# Main_MCU_ATSAME54.net
KiCad netlist of a schematic drawn in Altium Designer
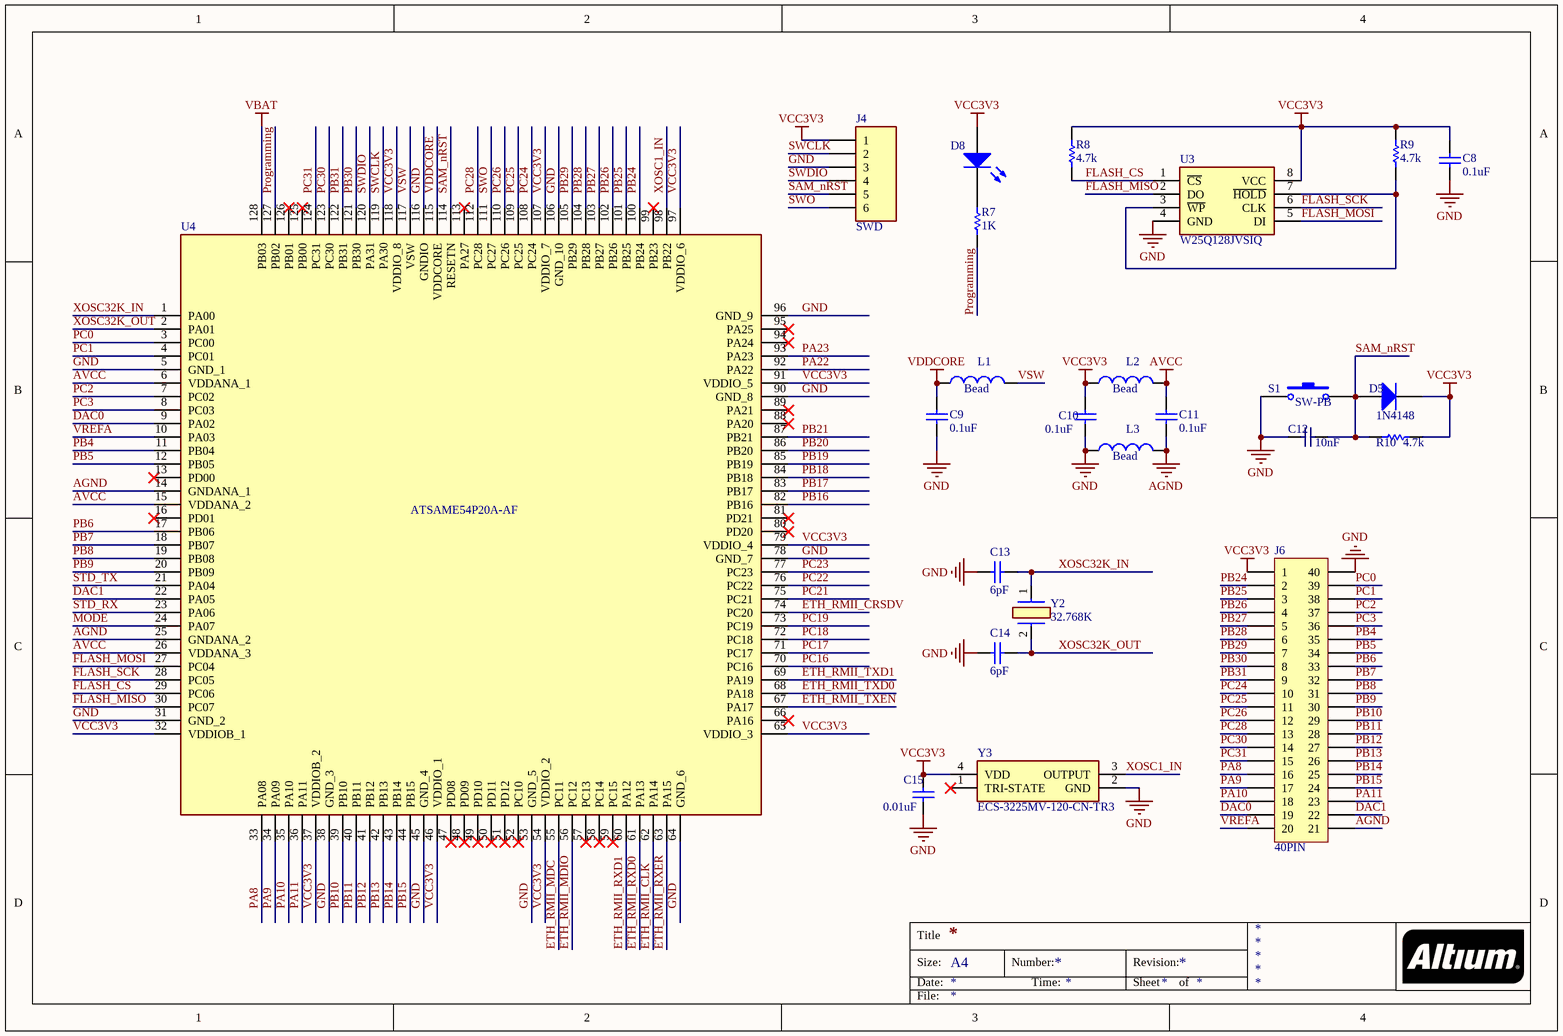
[diagram p0: Main_MCU_ATSAME54.SchDoc]

(export (version "E")
  (design (tool "Eeschema 10.0.6"))
  (components
    (comp (ref "C8")
      (value "0.1uF")
      (footprint "SMD0603")
      (description "Capacitor (Semiconductor SIM Model)")
      (fields (field (name "PUBLISHER") "Altium Limited"))
      (libsource (lib "Miscellaneous Devices") (part "Cap Semi"))
    )
    (comp (ref "C9")
      (value "0.1uF")
      (footprint "SMD0603")
      (description "Capacitor (Semiconductor SIM Model)")
      (fields (field (name "PUBLISHER") "Altium Limited"))
      (libsource (lib "Miscellaneous Devices") (part "Cap Semi"))
    )
    (comp (ref "C10")
      (value "0.1uF")
      (footprint "SMD0603")
      (description "Capacitor (Semiconductor SIM Model)")
      (fields (field (name "PUBLISHER") "Altium Limited"))
      (libsource (lib "Miscellaneous Devices") (part "Cap Semi"))
    )
    (comp (ref "C11")
      (value "0.1uF")
      (footprint "SMD0603")
      (description "Capacitor (Semiconductor SIM Model)")
      (fields (field (name "PUBLISHER") "Altium Limited"))
      (libsource (lib "Miscellaneous Devices") (part "Cap Semi"))
    )
    (comp (ref "C12")
      (value "10nF")
      (footprint "SMD0603")
      (description "Capacitor (Semiconductor SIM Model)")
      (libsource (lib "SRV8") (part "Cap"))
    )
    (comp (ref "C13")
      (value "6pF")
      (footprint "SMD0603")
      (description "Capacitor (Semiconductor SIM Model)")
      (fields (field (name "PUBLISHER") "Altium Limited"))
      (libsource (lib "Miscellaneous Devices") (part "Cap Semi"))
    )
    (comp (ref "C14")
      (value "6pF")
      (footprint "SMD0603")
      (description "Capacitor (Semiconductor SIM Model)")
      (fields (field (name "PUBLISHER") "Altium Limited"))
      (libsource (lib "Miscellaneous Devices") (part "Cap Semi"))
    )
    (comp (ref "C15")
      (value "0.01uF")
      (footprint "SMD0603")
      (description "Capacitor (Semiconductor SIM Model)")
      (fields (field (name "PUBLISHER") "Altium Limited"))
      (libsource (lib "Miscellaneous Devices") (part "Cap Semi"))
    )
    (comp (ref "D5")
      (value "1N4148")
      (footprint "1N4148")
      (description "Diode")
      (fields (field (name "PUBLISHER") "Altium Limited"))
      (libsource (lib "SRV8") (part "Diode 1N4148"))
    )
    (comp (ref "D8")
      (value "LED0")
      (footprint "SMD0603_LED")
      (description "Typical INFRARED GaAs LED")
      (fields (field (name "PUBLISHER") "Altium Limited"))
      (libsource (lib "Miscellaneous Devices") (part "LED0"))
    )
    (comp (ref "J4") (value "SWD") (footprint "ISP") (libsource (lib "ATSAME54p20a_Ethernet") (part "SWD")))
    (comp (ref "J6")
      (value "40PIN")
      (footprint "40PIN")
      (libsource (lib "ATSAME54p20a_Ethernet") (part "2x20_header"))
    )
    (comp (ref "L1")
      (value "Bead")
      (footprint "SMD0603")
      (description "Inductor")
      (fields (field (name "PUBLISHER") "Altium Limited"))
      (libsource (lib "Miscellaneous Devices") (part "Inductor"))
    )
    (comp (ref "L2")
      (value "Bead")
      (footprint "SMD0603")
      (description "Inductor")
      (fields (field (name "PUBLISHER") "Altium Limited"))
      (libsource (lib "Miscellaneous Devices") (part "Inductor"))
    )
    (comp (ref "L3")
      (value "Bead")
      (footprint "SMD0603")
      (description "Inductor")
      (fields (field (name "PUBLISHER") "Altium Limited"))
      (libsource (lib "Miscellaneous Devices") (part "Inductor"))
    )
    (comp (ref "R7")
      (value "1K")
      (footprint "SMD0603")
      (description "Semiconductor Resistor")
      (fields (field (name "PUBLISHER") "Altium Limited"))
      (libsource (lib "Miscellaneous Devices") (part "Res Semi"))
    )
    (comp (ref "R8")
      (value "4.7k")
      (footprint "SMD0603")
      (description "Semiconductor Resistor")
      (libsource (lib "*") (part "Res"))
    )
    (comp (ref "R9")
      (value "4.7k")
      (footprint "SMD0603")
      (description "Semiconductor Resistor")
      (libsource (lib "*") (part "Res"))
    )
    (comp (ref "R10")
      (value "4.7k")
      (footprint "SMD0603")
      (description "Semiconductor Resistor")
      (fields (field (name "Comment") "4.7K"))
      (libsource (lib "*") (part "Res"))
    )
    (comp (ref "S1")
      (value "SW-PB")
      (footprint "Button")
      (description "Switch")
      (fields (field (name "PUBLISHER") "Altium Limited"))
      (libsource (lib "Miscellaneous Devices") (part "SW-PB"))
    )
    (comp (ref "U3")
      (value "W25Q128JVSIQ")
      (footprint "ATSAME54p20a_Ethernet:SOIC127P790X216-8N")
      (description "Integrated Circuit")
      (fields (field (name "MOUSER2 PART NUMBER") "454-W25Q128JVSIQ"))
      (libsource (lib "ATSAME54p20a_Ethernet") (part "W25Q128JVSIQ"))
    )
    (comp (ref "U4")
      (value "ATSAME54P20A-AF")
      (footprint "QFP40P1600X1600X120-128N")
      (description "Integrated Circuit")
      (fields (field (name "MOUSER2 PART NUMBER") "556-ATSAME54P20A-AF"))
      (libsource (lib "ATSAME54p20a_Ethernet") (part "ATSAME54P20A-AF"))
    )
    (comp (ref "Y2")
      (value "32.768K")
      (footprint "ATSAME54p20a_Ethernet:ECS327634RTR")
      (description "Crystal or Oscillator")
      (fields (field (name "MANUFACTURER_PART_NUMBER") "ECS-.327-6-34R-TR"))
      (libsource (lib "ATSAME54_DEVB") (part "ECS-.327-6-34R-TR"))
    )
    (comp (ref "Y3")
      (value "ECS-3225MV-120-CN-TR3")
      (footprint "OSC3225")
      (description "Crystal or Oscillator")
      (libsource (lib "ATSAME54p20a_Ethernet") (part "ECS-3225MV-120-CN-TR3"))
    )
  )
  (nets
    (net (code "1") (name "/DAC0") (class "Default")
      (node (ref "J6") (pin "19") (pinfunction "19_19") (pintype "passive"))
      (node (ref "U4") (pin "9") (pinfunction "PA02_9") (pintype "passive"))
    )
    (net (code "2") (name "/DAC1") (class "Default")
      (node (ref "J6") (pin "22") (pinfunction "22_22") (pintype "passive"))
      (node (ref "U4") (pin "22") (pinfunction "PA05_22") (pintype "passive"))
    )
    (net (code "3") (name "/ETH_RMII_CLK") (class "Default")
      (node (ref "U4") (pin "62") (pinfunction "PA14_62") (pintype "passive"))
    )
    (net (code "4") (name "/ETH_RMII_CRSDV") (class "Default")
      (node (ref "U4") (pin "74") (pinfunction "PC20_74") (pintype "passive"))
    )
    (net (code "5") (name "/ETH_RMII_MDC") (class "Default")
      (node (ref "U4") (pin "55") (pinfunction "PC11_55") (pintype "passive"))
    )
    (net (code "6") (name "/ETH_RMII_MDIO") (class "Default")
      (node (ref "U4") (pin "56") (pinfunction "PC12_56") (pintype "passive"))
    )
    (net (code "7") (name "/ETH_RMII_RXD0") (class "Default")
      (node (ref "U4") (pin "61") (pinfunction "PA13_61") (pintype "passive"))
    )
    (net (code "8") (name "/ETH_RMII_RXD1") (class "Default")
      (node (ref "U4") (pin "60") (pinfunction "PA12_60") (pintype "passive"))
    )
    (net (code "9") (name "/ETH_RMII_RXER") (class "Default")
      (node (ref "U4") (pin "63") (pinfunction "PA15_63") (pintype "passive"))
    )
    (net (code "10") (name "/ETH_RMII_TXD0") (class "Default")
      (node (ref "U4") (pin "68") (pinfunction "PA18_68") (pintype "passive"))
    )
    (net (code "11") (name "/ETH_RMII_TXD1") (class "Default")
      (node (ref "U4") (pin "69") (pinfunction "PA19_69") (pintype "passive"))
    )
    (net (code "12") (name "/ETH_RMII_TXEN") (class "Default")
      (node (ref "U4") (pin "67") (pinfunction "PA17_67") (pintype "passive"))
    )
    (net (code "13") (name "/FLASH_CS") (class "Default")
      (node (ref "R8") (pin "1") (pinfunction "1_1") (pintype "passive"))
      (node (ref "U3") (pin "1") (pinfunction "~{CS}_1") (pintype "passive"))
      (node (ref "U4") (pin "29") (pinfunction "PC06_29") (pintype "passive"))
    )
    (net (code "14") (name "/FLASH_MISO") (class "Default")
      (node (ref "U3") (pin "2") (pinfunction "DO_2") (pintype "passive"))
      (node (ref "U4") (pin "30") (pinfunction "PC07_30") (pintype "passive"))
    )
    (net (code "15") (name "/FLASH_MOSI") (class "Default")
      (node (ref "U3") (pin "5") (pinfunction "DI_5") (pintype "passive"))
      (node (ref "U4") (pin "27") (pinfunction "PC04_27") (pintype "passive"))
    )
    (net (code "16") (name "/FLASH_SCK") (class "Default")
      (node (ref "U3") (pin "6") (pinfunction "CLK_6") (pintype "passive"))
      (node (ref "U4") (pin "28") (pinfunction "PC05_28") (pintype "passive"))
    )
    (net (code "17") (name "/MODE") (class "Default")
      (node (ref "U4") (pin "24") (pinfunction "PA07_24") (pintype "passive"))
    )
    (net (code "18") (name "/PA8") (class "Default")
      (node (ref "J6") (pin "16") (pinfunction "16_16") (pintype "passive"))
      (node (ref "U4") (pin "33") (pinfunction "PA08_33") (pintype "passive"))
    )
    (net (code "19") (name "/PA9") (class "Default")
      (node (ref "J6") (pin "17") (pinfunction "17_17") (pintype "passive"))
      (node (ref "U4") (pin "34") (pinfunction "PA09_34") (pintype "passive"))
    )
    (net (code "20") (name "/PA10") (class "Default")
      (node (ref "J6") (pin "18") (pinfunction "18_18") (pintype "passive"))
      (node (ref "U4") (pin "35") (pinfunction "PA10_35") (pintype "passive"))
    )
    (net (code "21") (name "/PA11") (class "Default")
      (node (ref "J6") (pin "23") (pinfunction "23_23") (pintype "passive"))
      (node (ref "U4") (pin "36") (pinfunction "PA11_36") (pintype "passive"))
    )
    (net (code "22") (name "/PA22") (class "Default")
      (node (ref "U4") (pin "92") (pinfunction "PA22_92") (pintype "passive"))
    )
    (net (code "23") (name "/PA23") (class "Default")
      (node (ref "U4") (pin "93") (pinfunction "PA23_93") (pintype "passive"))
    )
    (net (code "24") (name "/PB4") (class "Default")
      (node (ref "J6") (pin "35") (pinfunction "35_35") (pintype "passive"))
      (node (ref "U4") (pin "11") (pinfunction "PB04_11") (pintype "passive"))
    )
    (net (code "25") (name "/PB5") (class "Default")
      (node (ref "J6") (pin "34") (pinfunction "34_34") (pintype "passive"))
      (node (ref "U4") (pin "12") (pinfunction "PB05_12") (pintype "passive"))
    )
    (net (code "26") (name "/PB6") (class "Default")
      (node (ref "J6") (pin "33") (pinfunction "33_33") (pintype "passive"))
      (node (ref "U4") (pin "17") (pinfunction "PB06_17") (pintype "passive"))
    )
    (net (code "27") (name "/PB7") (class "Default")
      (node (ref "J6") (pin "32") (pinfunction "32_32") (pintype "passive"))
      (node (ref "U4") (pin "18") (pinfunction "PB07_18") (pintype "passive"))
    )
    (net (code "28") (name "/PB8") (class "Default")
      (node (ref "J6") (pin "31") (pinfunction "31_31") (pintype "passive"))
      (node (ref "U4") (pin "19") (pinfunction "PB08_19") (pintype "passive"))
    )
    (net (code "29") (name "/PB9") (class "Default")
      (node (ref "J6") (pin "30") (pinfunction "30_30") (pintype "passive"))
      (node (ref "U4") (pin "20") (pinfunction "PB09_20") (pintype "passive"))
    )
    (net (code "30") (name "/PB10") (class "Default")
      (node (ref "J6") (pin "29") (pinfunction "29_29") (pintype "passive"))
      (node (ref "U4") (pin "39") (pinfunction "PB10_39") (pintype "passive"))
    )
    (net (code "31") (name "/PB11") (class "Default")
      (node (ref "J6") (pin "28") (pinfunction "28_28") (pintype "passive"))
      (node (ref "U4") (pin "40") (pinfunction "PB11_40") (pintype "passive"))
    )
    (net (code "32") (name "/PB12") (class "Default")
      (node (ref "J6") (pin "27") (pinfunction "27_27") (pintype "passive"))
      (node (ref "U4") (pin "41") (pinfunction "PB12_41") (pintype "passive"))
    )
    (net (code "33") (name "/PB13") (class "Default")
      (node (ref "J6") (pin "26") (pinfunction "26_26") (pintype "passive"))
      (node (ref "U4") (pin "42") (pinfunction "PB13_42") (pintype "passive"))
    )
    (net (code "34") (name "/PB14") (class "Default")
      (node (ref "J6") (pin "25") (pinfunction "25_25") (pintype "passive"))
      (node (ref "U4") (pin "43") (pinfunction "PB14_43") (pintype "passive"))
    )
    (net (code "35") (name "/PB15") (class "Default")
      (node (ref "J6") (pin "24") (pinfunction "24_24") (pintype "passive"))
      (node (ref "U4") (pin "44") (pinfunction "PB15_44") (pintype "passive"))
    )
    (net (code "36") (name "/PB16") (class "Default")
      (node (ref "U4") (pin "82") (pinfunction "PB16_82") (pintype "passive"))
    )
    (net (code "37") (name "/PB17") (class "Default")
      (node (ref "U4") (pin "83") (pinfunction "PB17_83") (pintype "passive"))
    )
    (net (code "38") (name "/PB18") (class "Default")
      (node (ref "U4") (pin "84") (pinfunction "PB18_84") (pintype "passive"))
    )
    (net (code "39") (name "/PB19") (class "Default")
      (node (ref "U4") (pin "85") (pinfunction "PB19_85") (pintype "passive"))
    )
    (net (code "40") (name "/PB20") (class "Default")
      (node (ref "U4") (pin "86") (pinfunction "PB20_86") (pintype "passive"))
    )
    (net (code "41") (name "/PB21") (class "Default")
      (node (ref "U4") (pin "87") (pinfunction "PB21_87") (pintype "passive"))
    )
    (net (code "42") (name "/PB24") (class "Default")
      (node (ref "J6") (pin "2") (pinfunction "2_2") (pintype "passive"))
      (node (ref "U4") (pin "100") (pinfunction "PB24_100") (pintype "passive"))
    )
    (net (code "43") (name "/PB25") (class "Default")
      (node (ref "J6") (pin "3") (pinfunction "3_3") (pintype "passive"))
      (node (ref "U4") (pin "101") (pinfunction "PB25_101") (pintype "passive"))
    )
    (net (code "44") (name "/PB26") (class "Default")
      (node (ref "J6") (pin "4") (pinfunction "4_4") (pintype "passive"))
      (node (ref "U4") (pin "102") (pinfunction "PB26_102") (pintype "passive"))
    )
    (net (code "45") (name "/PB27") (class "Default")
      (node (ref "J6") (pin "5") (pinfunction "5_5") (pintype "passive"))
      (node (ref "U4") (pin "103") (pinfunction "PB27_103") (pintype "passive"))
    )
    (net (code "46") (name "/PB28") (class "Default")
      (node (ref "J6") (pin "6") (pinfunction "6_6") (pintype "passive"))
      (node (ref "U4") (pin "104") (pinfunction "PB28_104") (pintype "passive"))
    )
    (net (code "47") (name "/PB29") (class "Default")
      (node (ref "J6") (pin "7") (pinfunction "7_7") (pintype "passive"))
      (node (ref "U4") (pin "105") (pinfunction "PB29_105") (pintype "passive"))
    )
    (net (code "48") (name "/PB30") (class "Default")
      (node (ref "J6") (pin "8") (pinfunction "8_8") (pintype "passive"))
      (node (ref "U4") (pin "121") (pinfunction "PB30_121") (pintype "passive"))
    )
    (net (code "49") (name "/PB31") (class "Default")
      (node (ref "J6") (pin "9") (pinfunction "9_9") (pintype "passive"))
      (node (ref "U4") (pin "122") (pinfunction "PB31_122") (pintype "passive"))
    )
    (net (code "50") (name "/PC0") (class "Default")
      (node (ref "J6") (pin "39") (pinfunction "39_39") (pintype "passive"))
      (node (ref "U4") (pin "3") (pinfunction "PC00_3") (pintype "passive"))
    )
    (net (code "51") (name "/PC1") (class "Default")
      (node (ref "J6") (pin "38") (pinfunction "38_38") (pintype "passive"))
      (node (ref "U4") (pin "4") (pinfunction "PC01_4") (pintype "passive"))
    )
    (net (code "52") (name "/PC2") (class "Default")
      (node (ref "J6") (pin "37") (pinfunction "37_37") (pintype "passive"))
      (node (ref "U4") (pin "7") (pinfunction "PC02_7") (pintype "passive"))
    )
    (net (code "53") (name "/PC3") (class "Default")
      (node (ref "J6") (pin "36") (pinfunction "36_36") (pintype "passive"))
      (node (ref "U4") (pin "8") (pinfunction "PC03_8") (pintype "passive"))
    )
    (net (code "54") (name "/PC16") (class "Default")
      (node (ref "U4") (pin "70") (pinfunction "PC16_70") (pintype "passive"))
    )
    (net (code "55") (name "/PC17") (class "Default")
      (node (ref "U4") (pin "71") (pinfunction "PC17_71") (pintype "passive"))
    )
    (net (code "56") (name "/PC18") (class "Default")
      (node (ref "U4") (pin "72") (pinfunction "PC18_72") (pintype "passive"))
    )
    (net (code "57") (name "/PC19") (class "Default")
      (node (ref "U4") (pin "73") (pinfunction "PC19_73") (pintype "passive"))
    )
    (net (code "58") (name "/PC21") (class "Default")
      (node (ref "U4") (pin "75") (pinfunction "PC21_75") (pintype "passive"))
    )
    (net (code "59") (name "/PC22") (class "Default")
      (node (ref "U4") (pin "76") (pinfunction "PC22_76") (pintype "passive"))
    )
    (net (code "60") (name "/PC23") (class "Default")
      (node (ref "U4") (pin "77") (pinfunction "PC23_77") (pintype "passive"))
    )
    (net (code "61") (name "/PC24") (class "Default")
      (node (ref "J6") (pin "10") (pinfunction "10_10") (pintype "passive"))
      (node (ref "U4") (pin "108") (pinfunction "PC24_108") (pintype "passive"))
    )
    (net (code "62") (name "/PC25") (class "Default")
      (node (ref "J6") (pin "11") (pinfunction "11_11") (pintype "passive"))
      (node (ref "U4") (pin "109") (pinfunction "PC25_109") (pintype "passive"))
    )
    (net (code "63") (name "/PC26") (class "Default")
      (node (ref "J6") (pin "12") (pinfunction "12_12") (pintype "passive"))
      (node (ref "U4") (pin "110") (pinfunction "PC26_110") (pintype "passive"))
    )
    (net (code "64") (name "/PC28") (class "Default")
      (node (ref "J6") (pin "13") (pinfunction "13_13") (pintype "passive"))
      (node (ref "U4") (pin "112") (pinfunction "PC28_112") (pintype "passive"))
    )
    (net (code "65") (name "/PC30") (class "Default")
      (node (ref "J6") (pin "14") (pinfunction "14_14") (pintype "passive"))
      (node (ref "U4") (pin "123") (pinfunction "PC30_123") (pintype "passive"))
    )
    (net (code "66") (name "/PC31") (class "Default")
      (node (ref "J6") (pin "15") (pinfunction "15_15") (pintype "passive"))
      (node (ref "U4") (pin "124") (pinfunction "PC31_124") (pintype "passive"))
    )
    (net (code "67") (name "/Programming") (class "Default")
      (node (ref "R7") (pin "1") (pinfunction "1_1") (pintype "passive"))
      (node (ref "U4") (pin "127") (pinfunction "PB02_127") (pintype "passive"))
    )
    (net (code "68") (name "/SAM_nRST") (class "Default")
      (node (ref "C12") (pin "2") (pinfunction "2_2") (pintype "passive"))
      (node (ref "D5") (pin "1") (pinfunction "1_1") (pintype "passive"))
      (node (ref "J4") (pin "5") (pinfunction "5_5") (pintype "passive"))
      (node (ref "R10") (pin "1") (pinfunction "1_1") (pintype "passive"))
      (node (ref "S1") (pin "2") (pinfunction "2_2") (pintype "passive"))
      (node (ref "U4") (pin "114") (pinfunction "RESETN_114") (pintype "passive"))
    )
    (net (code "69") (name "/STD_RX") (class "Default")
      (node (ref "U4") (pin "23") (pinfunction "PA06_23") (pintype "passive"))
    )
    (net (code "70") (name "/STD_TX") (class "Default")
      (node (ref "U4") (pin "21") (pinfunction "PA04_21") (pintype "passive"))
    )
    (net (code "71") (name "/SWCLK") (class "Default")
      (node (ref "J4") (pin "2") (pinfunction "2_2") (pintype "passive"))
      (node (ref "U4") (pin "119") (pinfunction "PA30_119") (pintype "passive"))
    )
    (net (code "72") (name "/SWDIO") (class "Default")
      (node (ref "J4") (pin "4") (pinfunction "4_4") (pintype "passive"))
      (node (ref "U4") (pin "120") (pinfunction "PA31_120") (pintype "passive"))
    )
    (net (code "73") (name "/SWO") (class "Default")
      (node (ref "J4") (pin "6") (pinfunction "6_6") (pintype "passive"))
      (node (ref "U4") (pin "111") (pinfunction "PC27_111") (pintype "passive"))
    )
    (net (code "74") (name "/VREFA") (class "Default")
      (node (ref "J6") (pin "20") (pinfunction "20_20") (pintype "passive"))
      (node (ref "U4") (pin "10") (pinfunction "PA03_10") (pintype "passive"))
    )
    (net (code "75") (name "/VSW") (class "Default")
      (node (ref "L1") (pin "2") (pinfunction "2_2") (pintype "passive"))
      (node (ref "U4") (pin "117") (pinfunction "VSW_117") (pintype "passive"))
    )
    (net (code "76") (name "/XOSC1_IN") (class "Default")
      (node (ref "U4") (pin "98") (pinfunction "PB22_98") (pintype "passive"))
      (node (ref "Y3") (pin "3") (pinfunction "OUTPUT_3") (pintype "passive"))
    )
    (net (code "77") (name "/XOSC32K_IN") (class "Default")
      (node (ref "C13") (pin "1") (pinfunction "1_1") (pintype "passive"))
      (node (ref "U4") (pin "1") (pinfunction "PA00_1") (pintype "passive"))
      (node (ref "Y2") (pin "1") (pinfunction "OUT/IN_1") (pintype "passive"))
    )
    (net (code "78") (name "/XOSC32K_OUT") (class "Default")
      (node (ref "C14") (pin "1") (pinfunction "1_1") (pintype "passive"))
      (node (ref "U4") (pin "2") (pinfunction "PA01_2") (pintype "passive"))
      (node (ref "Y2") (pin "2") (pinfunction "OUT/IN_2") (pintype "passive"))
    )
    (net (code "79") (name "AGND") (class "Default")
      (node (ref "C11") (pin "2") (pinfunction "2_2") (pintype "passive"))
      (node (ref "J6") (pin "21") (pinfunction "21_21") (pintype "passive"))
      (node (ref "L3") (pin "2") (pinfunction "2_2") (pintype "passive"))
      (node (ref "U4") (pin "14") (pinfunction "GNDANA_1_14") (pintype "passive"))
      (node (ref "U4") (pin "25") (pinfunction "GNDANA_2_25") (pintype "passive"))
    )
    (net (code "80") (name "AVCC") (class "Default")
      (node (ref "C11") (pin "1") (pinfunction "1_1") (pintype "passive"))
      (node (ref "L2") (pin "2") (pinfunction "2_2") (pintype "passive"))
      (node (ref "U4") (pin "15") (pinfunction "VDDANA_2_15") (pintype "passive"))
      (node (ref "U4") (pin "26") (pinfunction "VDDANA_3_26") (pintype "passive"))
      (node (ref "U4") (pin "6") (pinfunction "VDDANA_1_6") (pintype "passive"))
    )
    (net (code "81") (name "GND") (class "Default")
      (node (ref "C10") (pin "2") (pinfunction "2_2") (pintype "passive"))
      (node (ref "C12") (pin "1") (pinfunction "1_1") (pintype "passive"))
      (node (ref "C13") (pin "2") (pinfunction "2_2") (pintype "passive"))
      (node (ref "C14") (pin "2") (pinfunction "2_2") (pintype "passive"))
      (node (ref "C15") (pin "1") (pinfunction "1_1") (pintype "passive"))
      (node (ref "C8") (pin "2") (pinfunction "2_2") (pintype "passive"))
      (node (ref "C9") (pin "2") (pinfunction "2_2") (pintype "passive"))
      (node (ref "J4") (pin "3") (pinfunction "3_3") (pintype "passive"))
      (node (ref "J6") (pin "40") (pinfunction "40_40") (pintype "passive"))
      (node (ref "L3") (pin "1") (pinfunction "1_1") (pintype "passive"))
      (node (ref "S1") (pin "1") (pinfunction "1_1") (pintype "passive"))
      (node (ref "U3") (pin "4") (pinfunction "GND_4") (pintype "passive"))
      (node (ref "U4") (pin "106") (pinfunction "GND_10_106") (pintype "passive"))
      (node (ref "U4") (pin "116") (pinfunction "GNDIO_116") (pintype "passive"))
      (node (ref "U4") (pin "31") (pinfunction "GND_2_31") (pintype "passive"))
      (node (ref "U4") (pin "38") (pinfunction "GND_3_38") (pintype "passive"))
      (node (ref "U4") (pin "45") (pinfunction "GND_4_45") (pintype "passive"))
      (node (ref "U4") (pin "5") (pinfunction "GND_1_5") (pintype "passive"))
      (node (ref "U4") (pin "53") (pinfunction "GND_5_53") (pintype "passive"))
      (node (ref "U4") (pin "64") (pinfunction "GND_6_64") (pintype "passive"))
      (node (ref "U4") (pin "78") (pinfunction "GND_7_78") (pintype "passive"))
      (node (ref "U4") (pin "90") (pinfunction "GND_8_90") (pintype "passive"))
      (node (ref "U4") (pin "96") (pinfunction "GND_9_96") (pintype "passive"))
      (node (ref "Y3") (pin "2") (pinfunction "GND_2") (pintype "passive"))
    )
    (net (code "82") (name "Net-(D8-K)") (class "Default")
      (node (ref "D8") (pin "2") (pinfunction "K_2") (pintype "passive"))
      (node (ref "R7") (pin "2") (pinfunction "2_2") (pintype "passive"))
    )
    (net (code "83") (name "Net-(U3-~{HOLD})") (class "Default")
      (node (ref "R9") (pin "1") (pinfunction "1_1") (pintype "passive"))
      (node (ref "U3") (pin "3") (pinfunction "~{WP}_3") (pintype "passive"))
      (node (ref "U3") (pin "7") (pinfunction "~{HOLD}_7") (pintype "passive"))
    )
    (net (code "84") (name "VBAT") (class "Default")
      (node (ref "U4") (pin "128") (pinfunction "PB03_128") (pintype "passive"))
    )
    (net (code "85") (name "VCC3V3") (class "Default")
      (node (ref "C10") (pin "1") (pinfunction "1_1") (pintype "passive"))
      (node (ref "C15") (pin "2") (pinfunction "2_2") (pintype "passive"))
      (node (ref "C8") (pin "1") (pinfunction "1_1") (pintype "passive"))
      (node (ref "D5") (pin "2") (pinfunction "2_2") (pintype "passive"))
      (node (ref "D8") (pin "1") (pinfunction "A_1") (pintype "passive"))
      (node (ref "J4") (pin "1") (pinfunction "1_1") (pintype "passive"))
      (node (ref "J6") (pin "1") (pinfunction "1_1") (pintype "passive"))
      (node (ref "L2") (pin "1") (pinfunction "1_1") (pintype "passive"))
      (node (ref "R10") (pin "2") (pinfunction "2_2") (pintype "passive"))
      (node (ref "R8") (pin "2") (pinfunction "2_2") (pintype "passive"))
      (node (ref "R9") (pin "2") (pinfunction "2_2") (pintype "passive"))
      (node (ref "U3") (pin "8") (pinfunction "VCC_8") (pintype "passive"))
      (node (ref "U4") (pin "107") (pinfunction "VDDIO_7_107") (pintype "passive"))
      (node (ref "U4") (pin "118") (pinfunction "VDDIO_8_118") (pintype "passive"))
      (node (ref "U4") (pin "32") (pinfunction "VDDIOB_1_32") (pintype "passive"))
      (node (ref "U4") (pin "37") (pinfunction "VDDIOB_2_37") (pintype "passive"))
      (node (ref "U4") (pin "46") (pinfunction "VDDIO_1_46") (pintype "passive"))
      (node (ref "U4") (pin "54") (pinfunction "VDDIO_2_54") (pintype "passive"))
      (node (ref "U4") (pin "65") (pinfunction "VDDIO_3_65") (pintype "passive"))
      (node (ref "U4") (pin "79") (pinfunction "VDDIO_4_79") (pintype "passive"))
      (node (ref "U4") (pin "91") (pinfunction "VDDIO_5_91") (pintype "passive"))
      (node (ref "U4") (pin "97") (pinfunction "VDDIO_6_97") (pintype "passive"))
      (node (ref "Y3") (pin "4") (pinfunction "VDD_4") (pintype "passive"))
    )
    (net (code "86") (name "VDDCORE") (class "Default")
      (node (ref "C9") (pin "1") (pinfunction "1_1") (pintype "passive"))
      (node (ref "L1") (pin "1") (pinfunction "1_1") (pintype "passive"))
      (node (ref "U4") (pin "115") (pinfunction "VDDCORE_115") (pintype "passive"))
    )
    (net (code "87") (name "unconnected-(U4-PA16-Pad66)") (class "Default")
      (node (ref "U4") (pin "66") (pinfunction "PA16_66") (pintype "passive+no_connect"))
    )
    (net (code "88") (name "unconnected-(U4-PA20-Pad88)") (class "Default")
      (node (ref "U4") (pin "88") (pinfunction "PA20_88") (pintype "passive+no_connect"))
    )
    (net (code "89") (name "unconnected-(U4-PA21-Pad89)") (class "Default")
      (node (ref "U4") (pin "89") (pinfunction "PA21_89") (pintype "passive+no_connect"))
    )
    (net (code "90") (name "unconnected-(U4-PA24-Pad94)") (class "Default")
      (node (ref "U4") (pin "94") (pinfunction "PA24_94") (pintype "passive+no_connect"))
    )
    (net (code "91") (name "unconnected-(U4-PA25-Pad95)") (class "Default")
      (node (ref "U4") (pin "95") (pinfunction "PA25_95") (pintype "passive+no_connect"))
    )
    (net (code "92") (name "unconnected-(U4-PA27-Pad113)") (class "Default")
      (node (ref "U4") (pin "113") (pinfunction "PA27_113") (pintype "passive+no_connect"))
    )
    (net (code "93") (name "unconnected-(U4-PB00-Pad125)") (class "Default")
      (node (ref "U4") (pin "125") (pinfunction "PB00_125") (pintype "passive+no_connect"))
    )
    (net (code "94") (name "unconnected-(U4-PB01-Pad126)") (class "Default")
      (node (ref "U4") (pin "126") (pinfunction "PB01_126") (pintype "passive+no_connect"))
    )
    (net (code "95") (name "unconnected-(U4-PB23-Pad99)") (class "Default")
      (node (ref "U4") (pin "99") (pinfunction "PB23_99") (pintype "passive+no_connect"))
    )
    (net (code "96") (name "unconnected-(U4-PC10-Pad52)") (class "Default")
      (node (ref "U4") (pin "52") (pinfunction "PC10_52") (pintype "passive+no_connect"))
    )
    (net (code "97") (name "unconnected-(U4-PC13-Pad57)") (class "Default")
      (node (ref "U4") (pin "57") (pinfunction "PC13_57") (pintype "passive+no_connect"))
    )
    (net (code "98") (name "unconnected-(U4-PC14-Pad58)") (class "Default")
      (node (ref "U4") (pin "58") (pinfunction "PC14_58") (pintype "passive+no_connect"))
    )
    (net (code "99") (name "unconnected-(U4-PC15-Pad59)") (class "Default")
      (node (ref "U4") (pin "59") (pinfunction "PC15_59") (pintype "passive+no_connect"))
    )
    (net (code "100") (name "unconnected-(U4-PD00-Pad13)") (class "Default")
      (node (ref "U4") (pin "13") (pinfunction "PD00_13") (pintype "passive+no_connect"))
    )
    (net (code "101") (name "unconnected-(U4-PD01-Pad16)") (class "Default")
      (node (ref "U4") (pin "16") (pinfunction "PD01_16") (pintype "passive+no_connect"))
    )
    (net (code "102") (name "unconnected-(U4-PD08-Pad47)") (class "Default")
      (node (ref "U4") (pin "47") (pinfunction "PD08_47") (pintype "passive+no_connect"))
    )
    (net (code "103") (name "unconnected-(U4-PD09-Pad48)") (class "Default")
      (node (ref "U4") (pin "48") (pinfunction "PD09_48") (pintype "passive+no_connect"))
    )
    (net (code "104") (name "unconnected-(U4-PD10-Pad49)") (class "Default")
      (node (ref "U4") (pin "49") (pinfunction "PD10_49") (pintype "passive+no_connect"))
    )
    (net (code "105") (name "unconnected-(U4-PD11-Pad50)") (class "Default")
      (node (ref "U4") (pin "50") (pinfunction "PD11_50") (pintype "passive+no_connect"))
    )
    (net (code "106") (name "unconnected-(U4-PD12-Pad51)") (class "Default")
      (node (ref "U4") (pin "51") (pinfunction "PD12_51") (pintype "passive+no_connect"))
    )
    (net (code "107") (name "unconnected-(U4-PD20-Pad80)") (class "Default")
      (node (ref "U4") (pin "80") (pinfunction "PD20_80") (pintype "passive+no_connect"))
    )
    (net (code "108") (name "unconnected-(U4-PD21-Pad81)") (class "Default")
      (node (ref "U4") (pin "81") (pinfunction "PD21_81") (pintype "passive+no_connect"))
    )
    (net (code "109") (name "unconnected-(Y3-TRI-STATE-Pad1)") (class "Default")
      (node (ref "Y3") (pin "1") (pinfunction "TRI-STATE_1") (pintype "passive+no_connect"))
    )
  )
)
